# ProPrj_Simon_memory_game_by_SAAD_2026-03.net
KiCad netlist of a schematic drawn in EasyEDA Pro
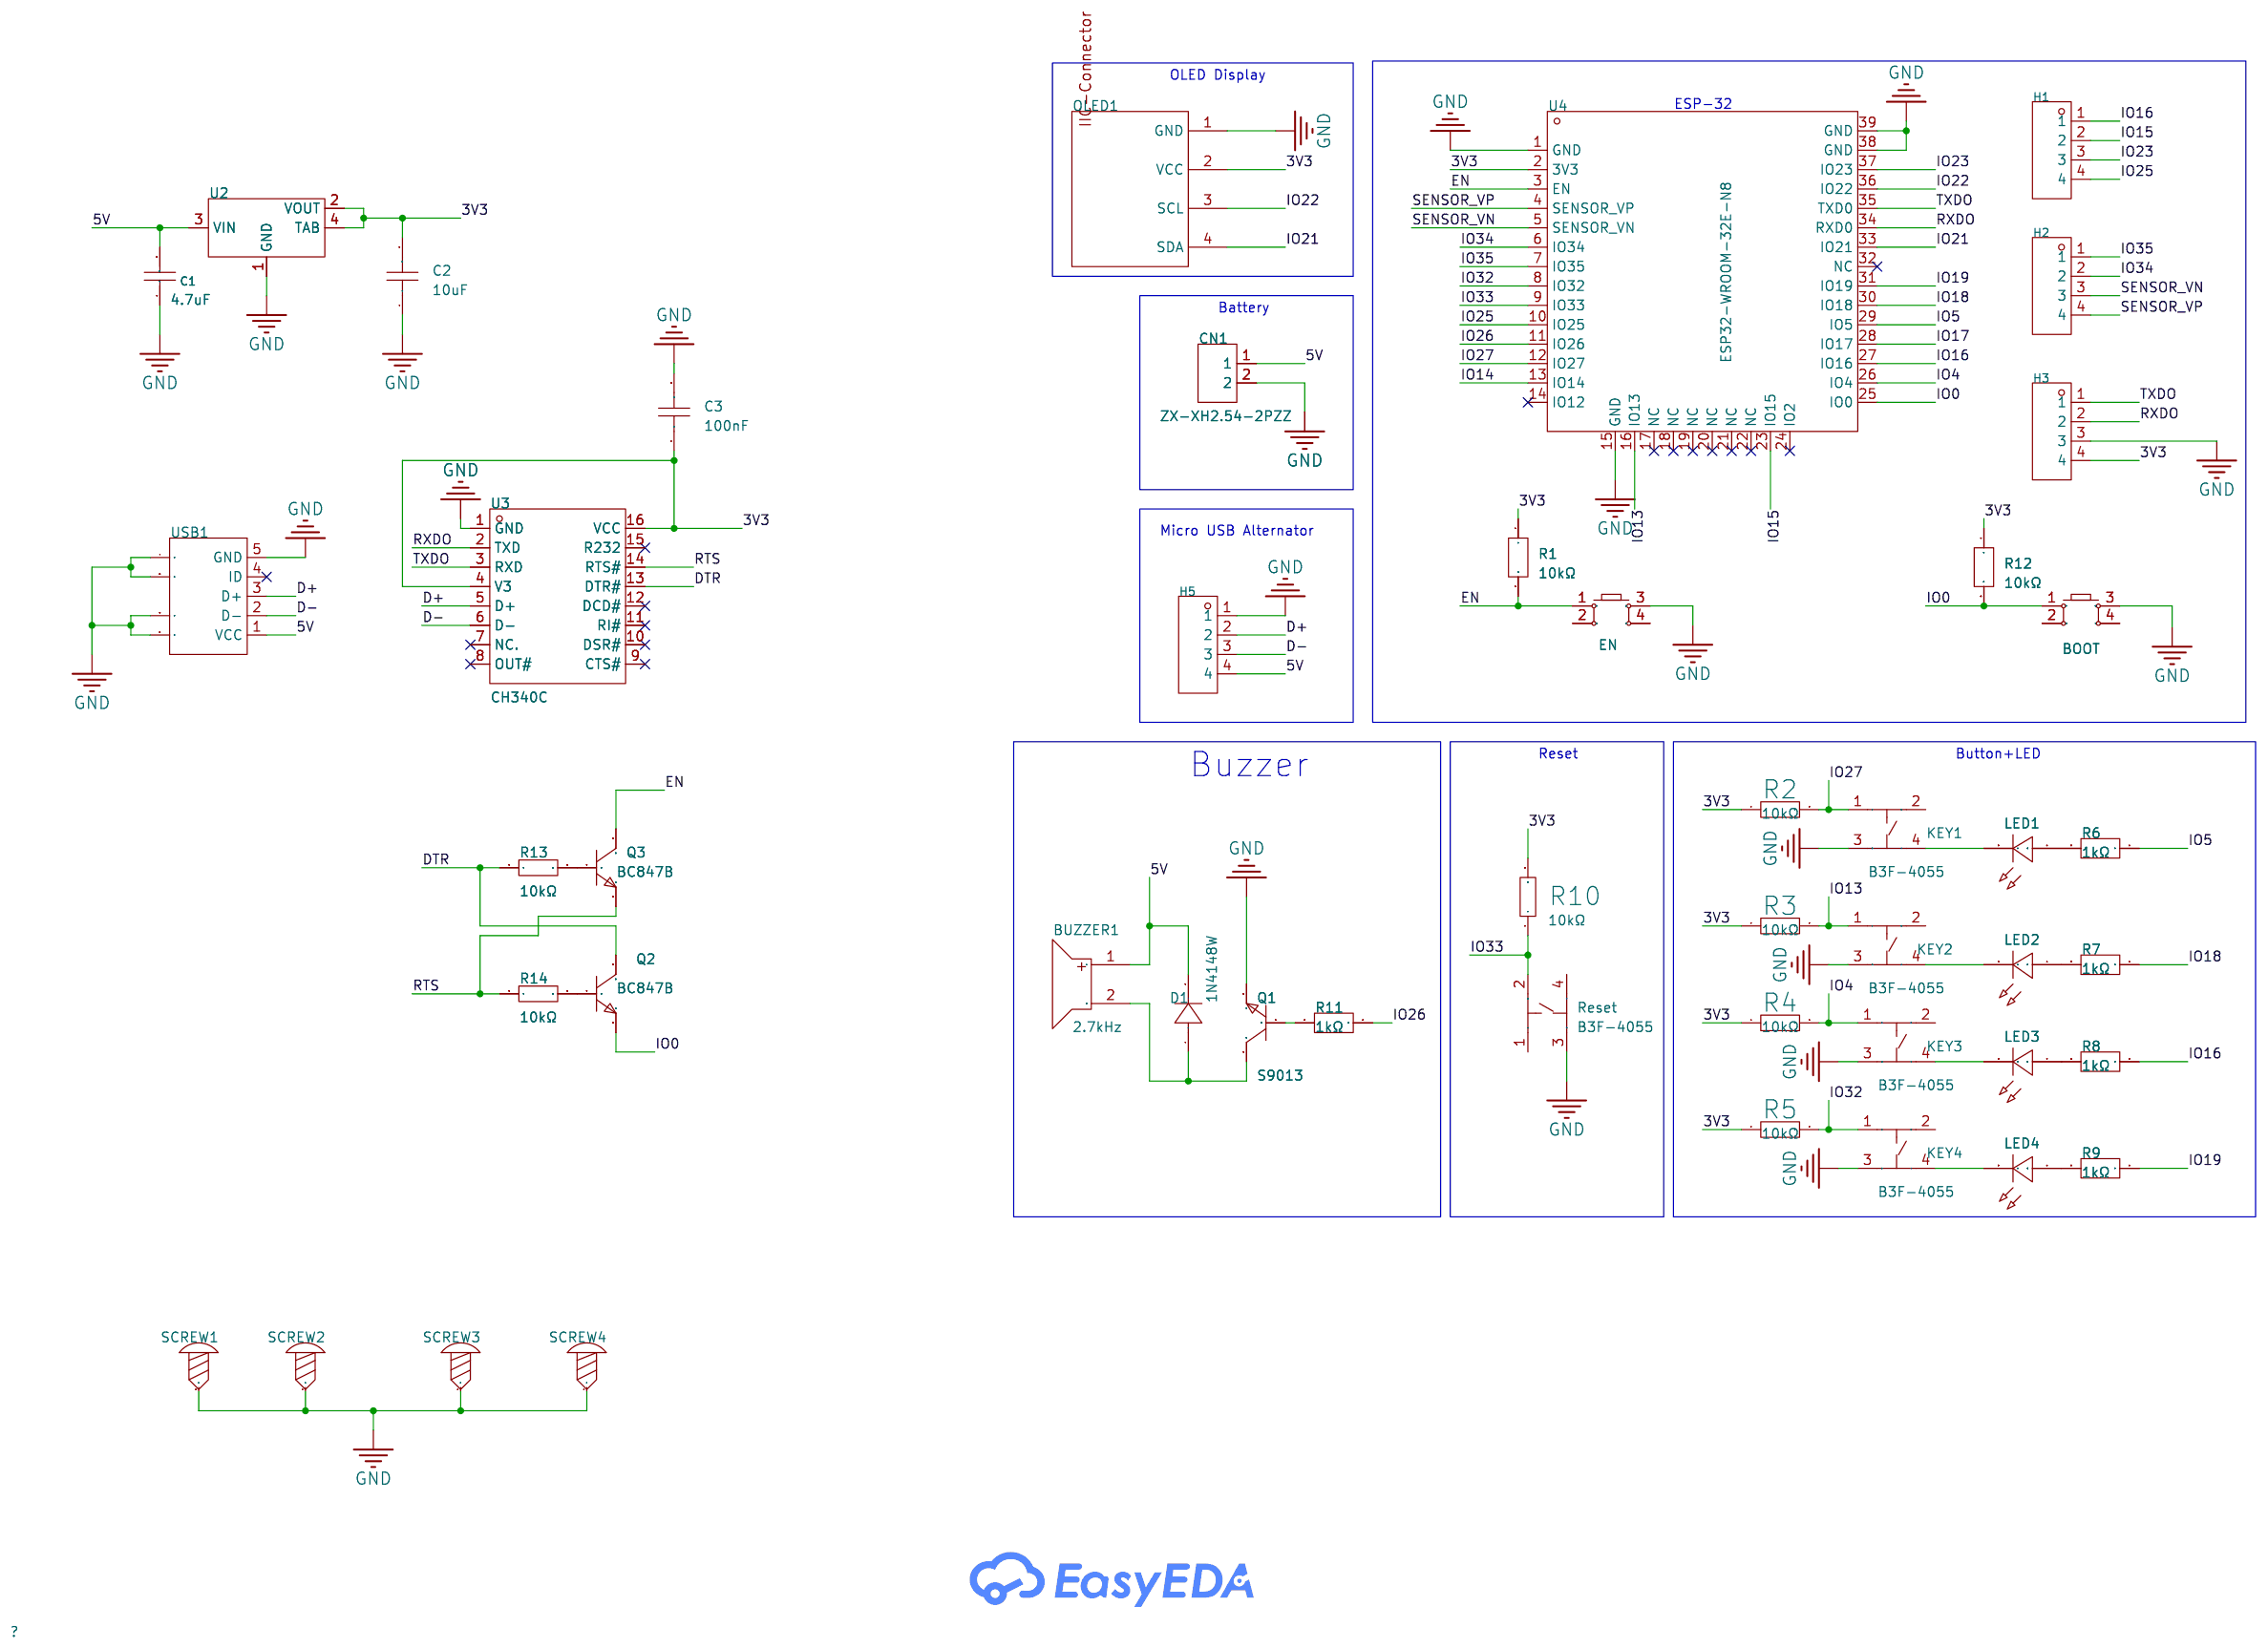
[diagram p0: schematic sheet]

(export (version "E")
  (design (tool "Eeschema 10.0.6"))
  (components
    (comp (ref "BOOT")
      (value "~")
      (footprint "easyedapro:SW-SMD_4P-L6.0-W6.0-P4.50-LS9.0-2")
      (libsource (lib "easyedapro") (part "轻触按键"))
    )
    (comp (ref "BUZZER1")
      (value "2.7kHz")
      (footprint "easyedapro:BUZ-TH_BD9.0-P4.00-D0.6-FD")
      (fields (field (name "Manufacturer Part") "QMB-09B-03") (field (name "Manufacturer") "华能"))
      (libsource (lib "easyedapro") (part "QMB-09B-03"))
    )
    (comp (ref "C1")
      (value "4.7uF")
      (footprint "easyedapro:C0603")
      (description "Capacitance:4.7uF Tolerance:±10% Tolerance:±10% Voltage Rating:10V Temperature Coefficient:X5R")
      (fields
        (field (name "Manufacturer Part") "CL10A475KP8NNNC")
        (field (name "Manufacturer") "SAMSUNG(三星)")
      )
      (libsource (lib "easyedapro") (part "CL10A475KP8NNNC"))
    )
    (comp (ref "C2")
      (value "10uF")
      (footprint "easyedapro:C0603")
      (description "Capacitance:10uF Tolerance:±10% Tolerance:±10% Voltage Rating:10V Temperature Coefficient:X5R")
      (fields
        (field (name "Manufacturer Part") "CL10A106KP8NNNC")
        (field (name "Manufacturer") "SAMSUNG(三星)")
      )
      (libsource (lib "easyedapro") (part "CL10A106KP8NNNC"))
    )
    (comp (ref "C3")
      (value "100nF")
      (footprint "easyedapro:C0603")
      (description "Capacitance:100nF Tolerance:±10% Tolerance:±10% Voltage Rating:50V Temperature Coefficient:X7R")
      (fields
        (field (name "Manufacturer Part") "CC0603KRX7R9BB104")
        (field (name "Manufacturer") "YAGEO(国巨)")
      )
      (libsource (lib "easyedapro") (part "CC0603KRX7R9BB104"))
    )
    (comp (ref "CN1")
      (value "ZX-XH2.54-2PZZ")
      (footprint "easyedapro:CONN-TH_2P-P2.50_HX25003-2A")
      (fields (field (name "Manufacturer") "Megastar(兆星)"))
      (libsource (lib "easyedapro") (part "ZX-XH2.54-2PZZ"))
    )
    (comp (ref "D1")
      (value "1N4148W")
      (footprint "easyedapro:SOD-123_L2.7-W1.6-LS3.7-FD")
      (fields (field (name "Manufacturer") "HXY MOSFET(华轩阳电子)"))
      (libsource (lib "easyedapro") (part "1N4148W_C5345962"))
    )
    (comp (ref "EN")
      (value "~")
      (footprint "easyedapro:SW-SMD_4P-L6.0-W6.0-P4.50-LS9.0-2")
      (libsource (lib "easyedapro") (part "轻触按键"))
    )
    (comp (ref "H1")
      (value "PZ254V-11-04P")
      (footprint "easyedapro:HDR-TH_4P-P2.54-V-M")
      (fields (field (name "Manufacturer") "XFCN(兴飞)"))
      (libsource (lib "easyedapro") (part "PZ254V-11-04P_C2691448"))
    )
    (comp (ref "H2")
      (value "PZ254V-11-04P")
      (footprint "easyedapro:HDR-TH_4P-P2.54-V-M")
      (fields (field (name "Manufacturer") "XFCN(兴飞)"))
      (libsource (lib "easyedapro") (part "PZ254V-11-04P_C2691448"))
    )
    (comp (ref "H3")
      (value "PZ254V-11-04P")
      (footprint "easyedapro:HDR-TH_4P-P2.54-V-M")
      (fields (field (name "Manufacturer") "XFCN(兴飞)"))
      (libsource (lib "easyedapro") (part "PZ254V-11-04P_C2691448"))
    )
    (comp (ref "H5")
      (value "PZ254V-11-04P")
      (footprint "easyedapro:HDR-TH_4P-P2.54-V-M")
      (fields (field (name "Manufacturer") "XFCN(兴飞)"))
      (libsource (lib "easyedapro") (part "PZ254V-11-04P_C2691448"))
    )
    (comp (ref "KEY1")
      (value "B3F-4055")
      (footprint "easyedapro:KEY-TH_4P-L12.0-W12.0-P5.00-LS13.4-EH")
      (fields (field (name "Manufacturer") "OMRON(欧姆龙)"))
      (libsource (lib "easyedapro") (part "B3F-4055"))
    )
    (comp (ref "KEY2")
      (value "B3F-4055")
      (footprint "easyedapro:KEY-TH_4P-L12.0-W12.0-P5.00-LS13.4-EH")
      (fields (field (name "Manufacturer") "OMRON(欧姆龙)"))
      (libsource (lib "easyedapro") (part "B3F-4055"))
    )
    (comp (ref "KEY3")
      (value "B3F-4055")
      (footprint "easyedapro:KEY-TH_4P-L12.0-W12.0-P5.00-LS13.4-EH")
      (fields (field (name "Manufacturer") "OMRON(欧姆龙)"))
      (libsource (lib "easyedapro") (part "B3F-4055"))
    )
    (comp (ref "KEY4")
      (value "B3F-4055")
      (footprint "easyedapro:KEY-TH_4P-L12.0-W12.0-P5.00-LS13.4-EH")
      (fields (field (name "Manufacturer") "OMRON(欧姆龙)"))
      (libsource (lib "easyedapro") (part "B3F-4055"))
    )
    (comp (ref "LED1")
      (value "~")
      (footprint "easyedapro:LED-TH_BD5.8-P2.54-FD")
      (libsource (lib "easyedapro") (part "LED_TH-R"))
    )
    (comp (ref "LED2")
      (value "~")
      (footprint "easyedapro:LED-TH_BD5.8-P2.54-FD")
      (libsource (lib "easyedapro") (part "LED_TH-R"))
    )
    (comp (ref "LED3")
      (value "~")
      (footprint "easyedapro:LED-TH_BD5.8-P2.54-FD")
      (libsource (lib "easyedapro") (part "LED_TH-R"))
    )
    (comp (ref "LED4")
      (value "~")
      (footprint "easyedapro:LED-TH_BD5.8-P2.54-FD")
      (libsource (lib "easyedapro") (part "LED_TH-R"))
    )
    (comp (ref "OLED1")
      (value "0.96OLED_4P_MODULE_JX")
      (footprint "easyedapro:0.96OLED_4P")
      (libsource (lib "easyedapro") (part "0.96OLED_4P_MODULE_JX"))
    )
    (comp (ref "Q1")
      (value "S9013")
      (footprint "easyedapro:SOT-23-3_L2.9-W1.3-P1.90-LS2.4-BR")
      (fields (field (name "Manufacturer") "HXY MOSFET(华轩阳电子)"))
      (libsource (lib "easyedapro") (part "S9013_C5184425"))
    )
    (comp (ref "Q2")
      (value "BC847B")
      (footprint "easyedapro:SOT-23-3_L2.9-W1.3-P1.90-LS2.4-BR")
      (fields (field (name "Manufacturer") "R+O(宏嘉诚)"))
      (libsource (lib "easyedapro") (part "BC847B_C20069135"))
    )
    (comp (ref "Q3")
      (value "BC847B")
      (footprint "easyedapro:SOT-23-3_L2.9-W1.3-P1.90-LS2.4-BR")
      (fields (field (name "Manufacturer") "R+O(宏嘉诚)"))
      (libsource (lib "easyedapro") (part "BC847B_C20069135"))
    )
    (comp (ref "R1")
      (value "10kΩ")
      (footprint "easyedapro:R0603")
      (fields (field (name "Manufacturer Part") "FRC0603F1001TS") (field (name "Manufacturer") "FOJAN(富捷)"))
      (libsource (lib "easyedapro") (part "FRC0603F1001TS"))
    )
    (comp (ref "R2")
      (value "10kΩ")
      (footprint "easyedapro:R0603")
      (fields
        (field (name "Manufacturer Part") "0603WAF1002T5E")
        (field (name "Manufacturer") "UNI-ROYAL(厚声)")
      )
      (libsource (lib "easyedapro") (part "0603WAF1002T5E"))
    )
    (comp (ref "R3")
      (value "10kΩ")
      (footprint "easyedapro:R0603")
      (fields
        (field (name "Manufacturer Part") "0603WAF1002T5E")
        (field (name "Manufacturer") "UNI-ROYAL(厚声)")
      )
      (libsource (lib "easyedapro") (part "0603WAF1002T5E"))
    )
    (comp (ref "R4")
      (value "10kΩ")
      (footprint "easyedapro:R0603")
      (fields
        (field (name "Manufacturer Part") "0603WAF1002T5E")
        (field (name "Manufacturer") "UNI-ROYAL(厚声)")
      )
      (libsource (lib "easyedapro") (part "0603WAF1002T5E"))
    )
    (comp (ref "R5")
      (value "10kΩ")
      (footprint "easyedapro:R0603")
      (fields
        (field (name "Manufacturer Part") "0603WAF1002T5E")
        (field (name "Manufacturer") "UNI-ROYAL(厚声)")
      )
      (libsource (lib "easyedapro") (part "0603WAF1002T5E"))
    )
    (comp (ref "R6")
      (value "1kΩ")
      (footprint "easyedapro:R0603")
      (fields (field (name "Manufacturer Part") "FRC0603F1001TS") (field (name "Manufacturer") "FOJAN(富捷)"))
      (libsource (lib "easyedapro") (part "FRC0603F1001TS"))
    )
    (comp (ref "R7")
      (value "1kΩ")
      (footprint "easyedapro:R0603")
      (fields (field (name "Manufacturer Part") "FRC0603F1001TS") (field (name "Manufacturer") "FOJAN(富捷)"))
      (libsource (lib "easyedapro") (part "FRC0603F1001TS"))
    )
    (comp (ref "R8")
      (value "1kΩ")
      (footprint "easyedapro:R0603")
      (fields (field (name "Manufacturer Part") "FRC0603F1001TS") (field (name "Manufacturer") "FOJAN(富捷)"))
      (libsource (lib "easyedapro") (part "FRC0603F1001TS"))
    )
    (comp (ref "R9")
      (value "1kΩ")
      (footprint "easyedapro:R0603")
      (fields (field (name "Manufacturer Part") "FRC0603F1001TS") (field (name "Manufacturer") "FOJAN(富捷)"))
      (libsource (lib "easyedapro") (part "FRC0603F1001TS"))
    )
    (comp (ref "R10")
      (value "10kΩ")
      (footprint "easyedapro:R0603")
      (fields
        (field (name "Manufacturer Part") "0603WAF1002T5E")
        (field (name "Manufacturer") "UNI-ROYAL(厚声)")
      )
      (libsource (lib "easyedapro") (part "0603WAF1002T5E"))
    )
    (comp (ref "R11")
      (value "1kΩ")
      (footprint "easyedapro:R0603")
      (fields (field (name "Manufacturer Part") "FRC0603F1001TS") (field (name "Manufacturer") "FOJAN(富捷)"))
      (libsource (lib "easyedapro") (part "FRC0603F1001TS"))
    )
    (comp (ref "R12")
      (value "10kΩ")
      (footprint "easyedapro:R0603")
      (fields (field (name "Manufacturer Part") "FRC0603F1001TS") (field (name "Manufacturer") "FOJAN(富捷)"))
      (libsource (lib "easyedapro") (part "FRC0603F1001TS"))
    )
    (comp (ref "R13")
      (value "10kΩ")
      (footprint "easyedapro:R_AXIAL-0.4")
      (libsource (lib "easyedapro") (part "Res"))
    )
    (comp (ref "R14")
      (value "10kΩ")
      (footprint "easyedapro:R_AXIAL-0.4")
      (libsource (lib "easyedapro") (part "Res"))
    )
    (comp (ref "Reset")
      (value "B3F-4055")
      (footprint "easyedapro:KEY-TH_4P-L12.0-W12.0-P5.00-LS13.4-EH")
      (fields (field (name "Manufacturer") "OMRON(欧姆龙)"))
      (libsource (lib "easyedapro") (part "B3F-4055"))
    )
    (comp (ref "SCREW1")
      (value "~")
      (footprint "easyedapro:Screw-Hole-M3")
      (libsource (lib "easyedapro") (part "Screw-Hole"))
    )
    (comp (ref "SCREW2")
      (value "~")
      (footprint "easyedapro:Screw-Hole-M3")
      (libsource (lib "easyedapro") (part "Screw-Hole"))
    )
    (comp (ref "SCREW3")
      (value "~")
      (footprint "easyedapro:Screw-Hole-M3")
      (libsource (lib "easyedapro") (part "Screw-Hole"))
    )
    (comp (ref "SCREW4")
      (value "~")
      (footprint "easyedapro:Screw-Hole-M3")
      (libsource (lib "easyedapro") (part "Screw-Hole"))
    )
    (comp (ref "U2")
      (value "~")
      (footprint "easyedapro:SOT-223_L6.7-W3.5-P2.30-BR")
      (libsource (lib "easyedapro") (part "AMS1117_OLD"))
    )
    (comp (ref "U3")
      (value "CH340C")
      (footprint "easyedapro:SOP-16_L10.0-W3.9-P1.27-LS6.0-BL")
      (fields (field (name "Manufacturer") "WCH(南京沁恒)"))
      (libsource (lib "easyedapro") (part "CH340C"))
    )
    (comp (ref "U4")
      (value "ESP32-WROOM-32E-N8")
      (fields (field (name "Manufacturer Part") "ESP32-WROOM-32E-N8-被合并"))
      (libsource (lib "easyedapro") (part "ESP32-WROOM-32E-N8"))
    )
    (comp (ref "USB1")
      (value "~")
      (footprint "easyedapro:MINI-USB-SMD_MINI-5PTP")
      (libsource (lib "easyedapro") (part "MINI 5PTP"))
    )
  )
  (nets
    (net (code "1") (name "/3V3") (class "Default")
      (node (ref "C2") (pin "2") (pinfunction "2_2") (pintype "unspecified"))
      (node (ref "C3") (pin "1") (pinfunction "1_1") (pintype "unspecified"))
      (node (ref "H3") (pin "4") (pinfunction "4_4") (pintype "input"))
      (node (ref "OLED1") (pin "2") (pinfunction "VCC_2") (pintype "unspecified"))
      (node (ref "R1") (pin "1") (pinfunction "1_1") (pintype "unspecified"))
      (node (ref "R10") (pin "2") (pinfunction "2_2") (pintype "input"))
      (node (ref "R12") (pin "1") (pinfunction "1_1") (pintype "unspecified"))
      (node (ref "R2") (pin "1") (pinfunction "1_1") (pintype "input"))
      (node (ref "R3") (pin "1") (pinfunction "1_1") (pintype "input"))
      (node (ref "R4") (pin "1") (pinfunction "1_1") (pintype "input"))
      (node (ref "R5") (pin "1") (pinfunction "1_1") (pintype "input"))
      (node (ref "U2") (pin "2") (pinfunction "VOUT_2") (pintype "input"))
      (node (ref "U2") (pin "4") (pinfunction "TAB_4") (pintype "input"))
      (node (ref "U3") (pin "16") (pinfunction "VCC_16") (pintype "unspecified"))
      (node (ref "U3") (pin "4") (pinfunction "V3_4") (pintype "unspecified"))
      (node (ref "U4") (pin "2") (pinfunction "3V3_2") (pintype "unspecified"))
    )
    (net (code "2") (name "/5V") (class "Default")
      (node (ref "BUZZER1") (pin "1") (pinfunction "1_1") (pintype "unspecified"))
      (node (ref "C1") (pin "2") (pinfunction "2_2") (pintype "input"))
      (node (ref "CN1") (pin "1") (pinfunction "1_1") (pintype "unspecified"))
      (node (ref "D1") (pin "2") (pinfunction "-_2") (pintype "unspecified"))
      (node (ref "H5") (pin "4") (pinfunction "4_4") (pintype "input"))
      (node (ref "U2") (pin "3") (pinfunction "VIN_3") (pintype "input"))
      (node (ref "USB1") (pin "1") (pinfunction "VCC_1") (pintype "input"))
    )
    (net (code "3") (name "/D+") (class "Default")
      (node (ref "H5") (pin "2") (pinfunction "2_2") (pintype "input"))
      (node (ref "U3") (pin "5") (pinfunction "D+_5") (pintype "unspecified"))
      (node (ref "USB1") (pin "3") (pinfunction "D+_3") (pintype "input"))
    )
    (net (code "4") (name "/D-") (class "Default")
      (node (ref "H5") (pin "3") (pinfunction "3_3") (pintype "input"))
      (node (ref "U3") (pin "6") (pinfunction "D-_6") (pintype "unspecified"))
      (node (ref "USB1") (pin "2") (pinfunction "D-_2") (pintype "input"))
    )
    (net (code "5") (name "/DTR") (class "Default")
      (node (ref "Q2") (pin "3") (pinfunction "C_3") (pintype "input"))
      (node (ref "R13") (pin "1") (pinfunction "1_1") (pintype "input"))
      (node (ref "U3") (pin "13") (pinfunction "DTR#_13") (pintype "unspecified"))
    )
    (net (code "6") (name "/EN") (class "Default")
      (node (ref "EN") (pin "1") (pinfunction "1_1") (pintype "input"))
      (node (ref "Q3") (pin "3") (pinfunction "C_3") (pintype "input"))
      (node (ref "R1") (pin "2") (pinfunction "2_2") (pintype "unspecified"))
      (node (ref "U4") (pin "3") (pinfunction "EN_3") (pintype "unspecified"))
    )
    (net (code "7") (name "/IO0") (class "Default")
      (node (ref "BOOT") (pin "1") (pinfunction "1_1") (pintype "input"))
      (node (ref "Q2") (pin "2") (pinfunction "E_2") (pintype "input"))
      (node (ref "R12") (pin "2") (pinfunction "2_2") (pintype "unspecified"))
      (node (ref "U4") (pin "25") (pinfunction "IO0_25") (pintype "unspecified"))
    )
    (net (code "8") (name "/IO4") (class "Default")
      (node (ref "KEY3") (pin "1") (pinfunction "1_1") (pintype "unspecified"))
      (node (ref "R4") (pin "2") (pinfunction "2_2") (pintype "input"))
      (node (ref "U4") (pin "26") (pinfunction "IO4_26") (pintype "unspecified"))
    )
    (net (code "9") (name "/IO5") (class "Default")
      (node (ref "R6") (pin "1") (pinfunction "1_1") (pintype "unspecified"))
      (node (ref "U4") (pin "29") (pinfunction "IO5_29") (pintype "unspecified"))
    )
    (net (code "10") (name "/IO13") (class "Default")
      (node (ref "KEY2") (pin "1") (pinfunction "1_1") (pintype "unspecified"))
      (node (ref "R3") (pin "2") (pinfunction "2_2") (pintype "input"))
      (node (ref "U4") (pin "16") (pinfunction "IO13_16") (pintype "unspecified"))
    )
    (net (code "11") (name "/IO14") (class "Default")
      (node (ref "U4") (pin "13") (pinfunction "IO14_13") (pintype "unspecified"))
    )
    (net (code "12") (name "/IO15") (class "Default")
      (node (ref "H1") (pin "2") (pinfunction "2_2") (pintype "input"))
      (node (ref "U4") (pin "23") (pinfunction "IO15_23") (pintype "unspecified"))
    )
    (net (code "13") (name "/IO16") (class "Default")
      (node (ref "H1") (pin "1") (pinfunction "1_1") (pintype "input"))
      (node (ref "R8") (pin "1") (pinfunction "1_1") (pintype "unspecified"))
      (node (ref "U4") (pin "27") (pinfunction "IO16_27") (pintype "unspecified"))
    )
    (net (code "14") (name "/IO17") (class "Default")
      (node (ref "U4") (pin "28") (pinfunction "IO17_28") (pintype "unspecified"))
    )
    (net (code "15") (name "/IO18") (class "Default")
      (node (ref "R7") (pin "1") (pinfunction "1_1") (pintype "unspecified"))
      (node (ref "U4") (pin "30") (pinfunction "IO18_30") (pintype "unspecified"))
    )
    (net (code "16") (name "/IO19") (class "Default")
      (node (ref "R9") (pin "1") (pinfunction "1_1") (pintype "unspecified"))
      (node (ref "U4") (pin "31") (pinfunction "IO19_31") (pintype "unspecified"))
    )
    (net (code "17") (name "/IO21") (class "Default")
      (node (ref "OLED1") (pin "4") (pinfunction "SDA_4") (pintype "unspecified"))
      (node (ref "U4") (pin "33") (pinfunction "IO21_33") (pintype "unspecified"))
    )
    (net (code "18") (name "/IO22") (class "Default")
      (node (ref "OLED1") (pin "3") (pinfunction "SCL_3") (pintype "unspecified"))
      (node (ref "U4") (pin "36") (pinfunction "IO22_36") (pintype "unspecified"))
    )
    (net (code "19") (name "/IO23") (class "Default")
      (node (ref "H1") (pin "3") (pinfunction "3_3") (pintype "input"))
      (node (ref "U4") (pin "37") (pinfunction "IO23_37") (pintype "unspecified"))
    )
    (net (code "20") (name "/IO25") (class "Default")
      (node (ref "H1") (pin "4") (pinfunction "4_4") (pintype "input"))
      (node (ref "U4") (pin "10") (pinfunction "IO25_10") (pintype "unspecified"))
    )
    (net (code "21") (name "/IO26") (class "Default")
      (node (ref "R11") (pin "1") (pinfunction "1_1") (pintype "unspecified"))
      (node (ref "U4") (pin "11") (pinfunction "IO26_11") (pintype "unspecified"))
    )
    (net (code "22") (name "/IO27") (class "Default")
      (node (ref "KEY1") (pin "1") (pinfunction "1_1") (pintype "unspecified"))
      (node (ref "R2") (pin "2") (pinfunction "2_2") (pintype "input"))
      (node (ref "U4") (pin "12") (pinfunction "IO27_12") (pintype "unspecified"))
    )
    (net (code "23") (name "/IO32") (class "Default")
      (node (ref "KEY4") (pin "1") (pinfunction "1_1") (pintype "unspecified"))
      (node (ref "R5") (pin "2") (pinfunction "2_2") (pintype "input"))
      (node (ref "U4") (pin "8") (pinfunction "IO32_8") (pintype "unspecified"))
    )
    (net (code "24") (name "/IO33") (class "Default")
      (node (ref "R10") (pin "1") (pinfunction "1_1") (pintype "input"))
      (node (ref "Reset") (pin "2") (pinfunction "2_2") (pintype "unspecified"))
      (node (ref "U4") (pin "9") (pinfunction "IO33_9") (pintype "unspecified"))
    )
    (net (code "25") (name "/IO34") (class "Default")
      (node (ref "H2") (pin "2") (pinfunction "2_2") (pintype "input"))
      (node (ref "U4") (pin "6") (pinfunction "IO34_6") (pintype "unspecified"))
    )
    (net (code "26") (name "/IO35") (class "Default")
      (node (ref "H2") (pin "1") (pinfunction "1_1") (pintype "input"))
      (node (ref "U4") (pin "7") (pinfunction "IO35_7") (pintype "unspecified"))
    )
    (net (code "27") (name "/RTS") (class "Default")
      (node (ref "Q3") (pin "2") (pinfunction "E_2") (pintype "input"))
      (node (ref "R14") (pin "1") (pinfunction "1_1") (pintype "input"))
      (node (ref "U3") (pin "14") (pinfunction "RTS#_14") (pintype "unspecified"))
    )
    (net (code "28") (name "/RXDO") (class "Default")
      (node (ref "H3") (pin "2") (pinfunction "2_2") (pintype "input"))
      (node (ref "U3") (pin "2") (pinfunction "TXD_2") (pintype "unspecified"))
      (node (ref "U4") (pin "34") (pinfunction "RXD0_34") (pintype "unspecified"))
    )
    (net (code "29") (name "/SENSOR_VN") (class "Default")
      (node (ref "H2") (pin "3") (pinfunction "3_3") (pintype "input"))
      (node (ref "U4") (pin "5") (pinfunction "SENSOR_VN_5") (pintype "unspecified"))
    )
    (net (code "30") (name "/SENSOR_VP") (class "Default")
      (node (ref "H2") (pin "4") (pinfunction "4_4") (pintype "input"))
      (node (ref "U4") (pin "4") (pinfunction "SENSOR_VP_4") (pintype "unspecified"))
    )
    (net (code "31") (name "/TXDO") (class "Default")
      (node (ref "H3") (pin "1") (pinfunction "1_1") (pintype "input"))
      (node (ref "U3") (pin "3") (pinfunction "RXD_3") (pintype "unspecified"))
      (node (ref "U4") (pin "35") (pinfunction "TXD0_35") (pintype "unspecified"))
    )
    (net (code "32") (name "GND") (class "Default")
      (node (ref "BOOT") (pin "3") (pinfunction "3_3") (pintype "input"))
      (node (ref "C1") (pin "1") (pinfunction "1_1") (pintype "input"))
      (node (ref "C2") (pin "1") (pinfunction "1_1") (pintype "unspecified"))
      (node (ref "C3") (pin "2") (pinfunction "2_2") (pintype "unspecified"))
      (node (ref "CN1") (pin "2") (pinfunction "2_2") (pintype "unspecified"))
      (node (ref "EN") (pin "3") (pinfunction "3_3") (pintype "input"))
      (node (ref "H3") (pin "3") (pinfunction "3_3") (pintype "input"))
      (node (ref "H5") (pin "1") (pinfunction "1_1") (pintype "input"))
      (node (ref "KEY1") (pin "3") (pinfunction "3_3") (pintype "unspecified"))
      (node (ref "KEY2") (pin "3") (pinfunction "3_3") (pintype "unspecified"))
      (node (ref "KEY3") (pin "3") (pinfunction "3_3") (pintype "unspecified"))
      (node (ref "KEY4") (pin "3") (pinfunction "3_3") (pintype "unspecified"))
      (node (ref "OLED1") (pin "1") (pinfunction "GND_1") (pintype "unspecified"))
      (node (ref "Q1") (pin "2") (pinfunction "E_2") (pintype "unspecified"))
      (node (ref "Reset") (pin "3") (pinfunction "3_3") (pintype "unspecified"))
      (node (ref "SCREW1") (pin "1") (pinfunction "1_1") (pintype "input"))
      (node (ref "SCREW2") (pin "1") (pinfunction "1_1") (pintype "input"))
      (node (ref "SCREW3") (pin "1") (pinfunction "1_1") (pintype "input"))
      (node (ref "SCREW4") (pin "1") (pinfunction "1_1") (pintype "input"))
      (node (ref "U2") (pin "1") (pinfunction "GND_1") (pintype "input"))
      (node (ref "U3") (pin "1") (pinfunction "GND_1") (pintype "unspecified"))
      (node (ref "U4") (pin "1") (pinfunction "GND_1") (pintype "unspecified"))
      (node (ref "U4") (pin "15") (pinfunction "GND_15") (pintype "unspecified"))
      (node (ref "U4") (pin "38") (pinfunction "GND_38") (pintype "unspecified"))
      (node (ref "U4") (pin "39") (pinfunction "GND_39") (pintype "unspecified"))
      (node (ref "USB1") (pin "5") (pinfunction "GND_5") (pintype "input"))
      (node (ref "USB1") (pin "6") (pinfunction "EH_6") (pintype "unspecified"))
      (node (ref "USB1") (pin "7") (pinfunction "EH_7") (pintype "unspecified"))
      (node (ref "USB1") (pin "8") (pinfunction "EH_8") (pintype "unspecified"))
      (node (ref "USB1") (pin "9") (pinfunction "EH_9") (pintype "unspecified"))
    )
    (net (code "33") (name "Net-(D1-+)") (class "Default")
      (node (ref "BUZZER1") (pin "2") (pinfunction "2_2") (pintype "unspecified"))
      (node (ref "D1") (pin "1") (pinfunction "+_1") (pintype "unspecified"))
      (node (ref "Q1") (pin "3") (pinfunction "C_3") (pintype "unspecified"))
    )
    (net (code "34") (name "Net-(LED1-A)") (class "Default")
      (node (ref "KEY1") (pin "4") (pinfunction "4_4") (pintype "unspecified"))
      (node (ref "LED1") (pin "2") (pinfunction "A_2") (pintype "input"))
    )
    (net (code "35") (name "Net-(LED1-C)") (class "Default")
      (node (ref "LED1") (pin "1") (pinfunction "C_1") (pintype "input"))
      (node (ref "R6") (pin "2") (pinfunction "2_2") (pintype "unspecified"))
    )
    (net (code "36") (name "Net-(LED2-A)") (class "Default")
      (node (ref "KEY2") (pin "4") (pinfunction "4_4") (pintype "unspecified"))
      (node (ref "LED2") (pin "2") (pinfunction "A_2") (pintype "input"))
    )
    (net (code "37") (name "Net-(LED2-C)") (class "Default")
      (node (ref "LED2") (pin "1") (pinfunction "C_1") (pintype "input"))
      (node (ref "R7") (pin "2") (pinfunction "2_2") (pintype "unspecified"))
    )
    (net (code "38") (name "Net-(LED3-A)") (class "Default")
      (node (ref "KEY3") (pin "4") (pinfunction "4_4") (pintype "unspecified"))
      (node (ref "LED3") (pin "2") (pinfunction "A_2") (pintype "input"))
    )
    (net (code "39") (name "Net-(LED3-C)") (class "Default")
      (node (ref "LED3") (pin "1") (pinfunction "C_1") (pintype "input"))
      (node (ref "R8") (pin "2") (pinfunction "2_2") (pintype "unspecified"))
    )
    (net (code "40") (name "Net-(LED4-A)") (class "Default")
      (node (ref "KEY4") (pin "4") (pinfunction "4_4") (pintype "unspecified"))
      (node (ref "LED4") (pin "2") (pinfunction "A_2") (pintype "input"))
    )
    (net (code "41") (name "Net-(LED4-C)") (class "Default")
      (node (ref "LED4") (pin "1") (pinfunction "C_1") (pintype "input"))
      (node (ref "R9") (pin "2") (pinfunction "2_2") (pintype "unspecified"))
    )
    (net (code "42") (name "Net-(Q1-B)") (class "Default")
      (node (ref "Q1") (pin "1") (pinfunction "B_1") (pintype "unspecified"))
      (node (ref "R11") (pin "2") (pinfunction "2_2") (pintype "unspecified"))
    )
    (net (code "43") (name "Net-(Q2-B)") (class "Default")
      (node (ref "Q2") (pin "1") (pinfunction "B_1") (pintype "input"))
      (node (ref "R14") (pin "2") (pinfunction "2_2") (pintype "input"))
    )
    (net (code "44") (name "Net-(Q3-B)") (class "Default")
      (node (ref "Q3") (pin "1") (pinfunction "B_1") (pintype "input"))
      (node (ref "R13") (pin "2") (pinfunction "2_2") (pintype "input"))
    )
    (net (code "45") (name "unconnected-(BOOT-Pad2)") (class "Default")
      (node (ref "BOOT") (pin "2") (pinfunction "2_2") (pintype "input"))
    )
    (net (code "46") (name "unconnected-(BOOT-Pad4)") (class "Default")
      (node (ref "BOOT") (pin "4") (pinfunction "4_4") (pintype "input"))
    )
    (net (code "47") (name "unconnected-(EN-Pad2)") (class "Default")
      (node (ref "EN") (pin "2") (pinfunction "2_2") (pintype "input"))
    )
    (net (code "48") (name "unconnected-(EN-Pad4)") (class "Default")
      (node (ref "EN") (pin "4") (pinfunction "4_4") (pintype "input"))
    )
    (net (code "49") (name "unconnected-(KEY1-Pad2)") (class "Default")
      (node (ref "KEY1") (pin "2") (pinfunction "2_2") (pintype "unspecified"))
    )
    (net (code "50") (name "unconnected-(KEY2-Pad2)") (class "Default")
      (node (ref "KEY2") (pin "2") (pinfunction "2_2") (pintype "unspecified"))
    )
    (net (code "51") (name "unconnected-(KEY3-Pad2)") (class "Default")
      (node (ref "KEY3") (pin "2") (pinfunction "2_2") (pintype "unspecified"))
    )
    (net (code "52") (name "unconnected-(KEY4-Pad2)") (class "Default")
      (node (ref "KEY4") (pin "2") (pinfunction "2_2") (pintype "unspecified"))
    )
    (net (code "53") (name "unconnected-(Reset-Pad1)") (class "Default")
      (node (ref "Reset") (pin "1") (pinfunction "1_1") (pintype "unspecified"))
    )
    (net (code "54") (name "unconnected-(Reset-Pad4)") (class "Default")
      (node (ref "Reset") (pin "4") (pinfunction "4_4") (pintype "unspecified"))
    )
    (net (code "55") (name "unconnected-(U3-CTS#-Pad9)") (class "Default")
      (node (ref "U3") (pin "9") (pinfunction "CTS#_9") (pintype "unspecified+no_connect"))
    )
    (net (code "56") (name "unconnected-(U3-DCD#-Pad12)") (class "Default")
      (node (ref "U3") (pin "12") (pinfunction "DCD#_12") (pintype "unspecified+no_connect"))
    )
    (net (code "57") (name "unconnected-(U3-DSR#-Pad10)") (class "Default")
      (node (ref "U3") (pin "10") (pinfunction "DSR#_10") (pintype "unspecified+no_connect"))
    )
    (net (code "58") (name "unconnected-(U3-NC.-Pad7)") (class "Default")
      (node (ref "U3") (pin "7") (pinfunction "NC._7") (pintype "unspecified+no_connect"))
    )
    (net (code "59") (name "unconnected-(U3-OUT#-Pad8)") (class "Default")
      (node (ref "U3") (pin "8") (pinfunction "OUT#_8") (pintype "unspecified+no_connect"))
    )
    (net (code "60") (name "unconnected-(U3-R232-Pad15)") (class "Default")
      (node (ref "U3") (pin "15") (pinfunction "R232_15") (pintype "unspecified+no_connect"))
    )
    (net (code "61") (name "unconnected-(U3-RI#-Pad11)") (class "Default")
      (node (ref "U3") (pin "11") (pinfunction "RI#_11") (pintype "unspecified+no_connect"))
    )
    (net (code "62") (name "unconnected-(U4-IO2-Pad24)") (class "Default")
      (node (ref "U4") (pin "24") (pinfunction "IO2_24") (pintype "unspecified+no_connect"))
    )
    (net (code "63") (name "unconnected-(U4-IO12-Pad14)") (class "Default")
      (node (ref "U4") (pin "14") (pinfunction "IO12_14") (pintype "unspecified+no_connect"))
    )
    (net (code "64") (name "unconnected-(U4-NC-Pad17)") (class "Default")
      (node (ref "U4") (pin "17") (pinfunction "NC_17") (pintype "unspecified+no_connect"))
    )
    (net (code "65") (name "unconnected-(U4-NC-Pad18)") (class "Default")
      (node (ref "U4") (pin "18") (pinfunction "NC_18") (pintype "unspecified+no_connect"))
    )
    (net (code "66") (name "unconnected-(U4-NC-Pad19)") (class "Default")
      (node (ref "U4") (pin "19") (pinfunction "NC_19") (pintype "unspecified+no_connect"))
    )
    (net (code "67") (name "unconnected-(U4-NC-Pad20)") (class "Default")
      (node (ref "U4") (pin "20") (pinfunction "NC_20") (pintype "unspecified+no_connect"))
    )
    (net (code "68") (name "unconnected-(U4-NC-Pad21)") (class "Default")
      (node (ref "U4") (pin "21") (pinfunction "NC_21") (pintype "unspecified+no_connect"))
    )
    (net (code "69") (name "unconnected-(U4-NC-Pad22)") (class "Default")
      (node (ref "U4") (pin "22") (pinfunction "NC_22") (pintype "unspecified+no_connect"))
    )
    (net (code "70") (name "unconnected-(U4-NC-Pad32)") (class "Default")
      (node (ref "U4") (pin "32") (pinfunction "NC_32") (pintype "unspecified+no_connect"))
    )
    (net (code "71") (name "unconnected-(USB1-ID-Pad4)") (class "Default")
      (node (ref "USB1") (pin "4") (pinfunction "ID_4") (pintype "input+no_connect"))
    )
  )
)
